# AVR128DB48_Curiosity_Nano_Target_MCU.net
KiCad netlist of a schematic drawn in Altium Designer
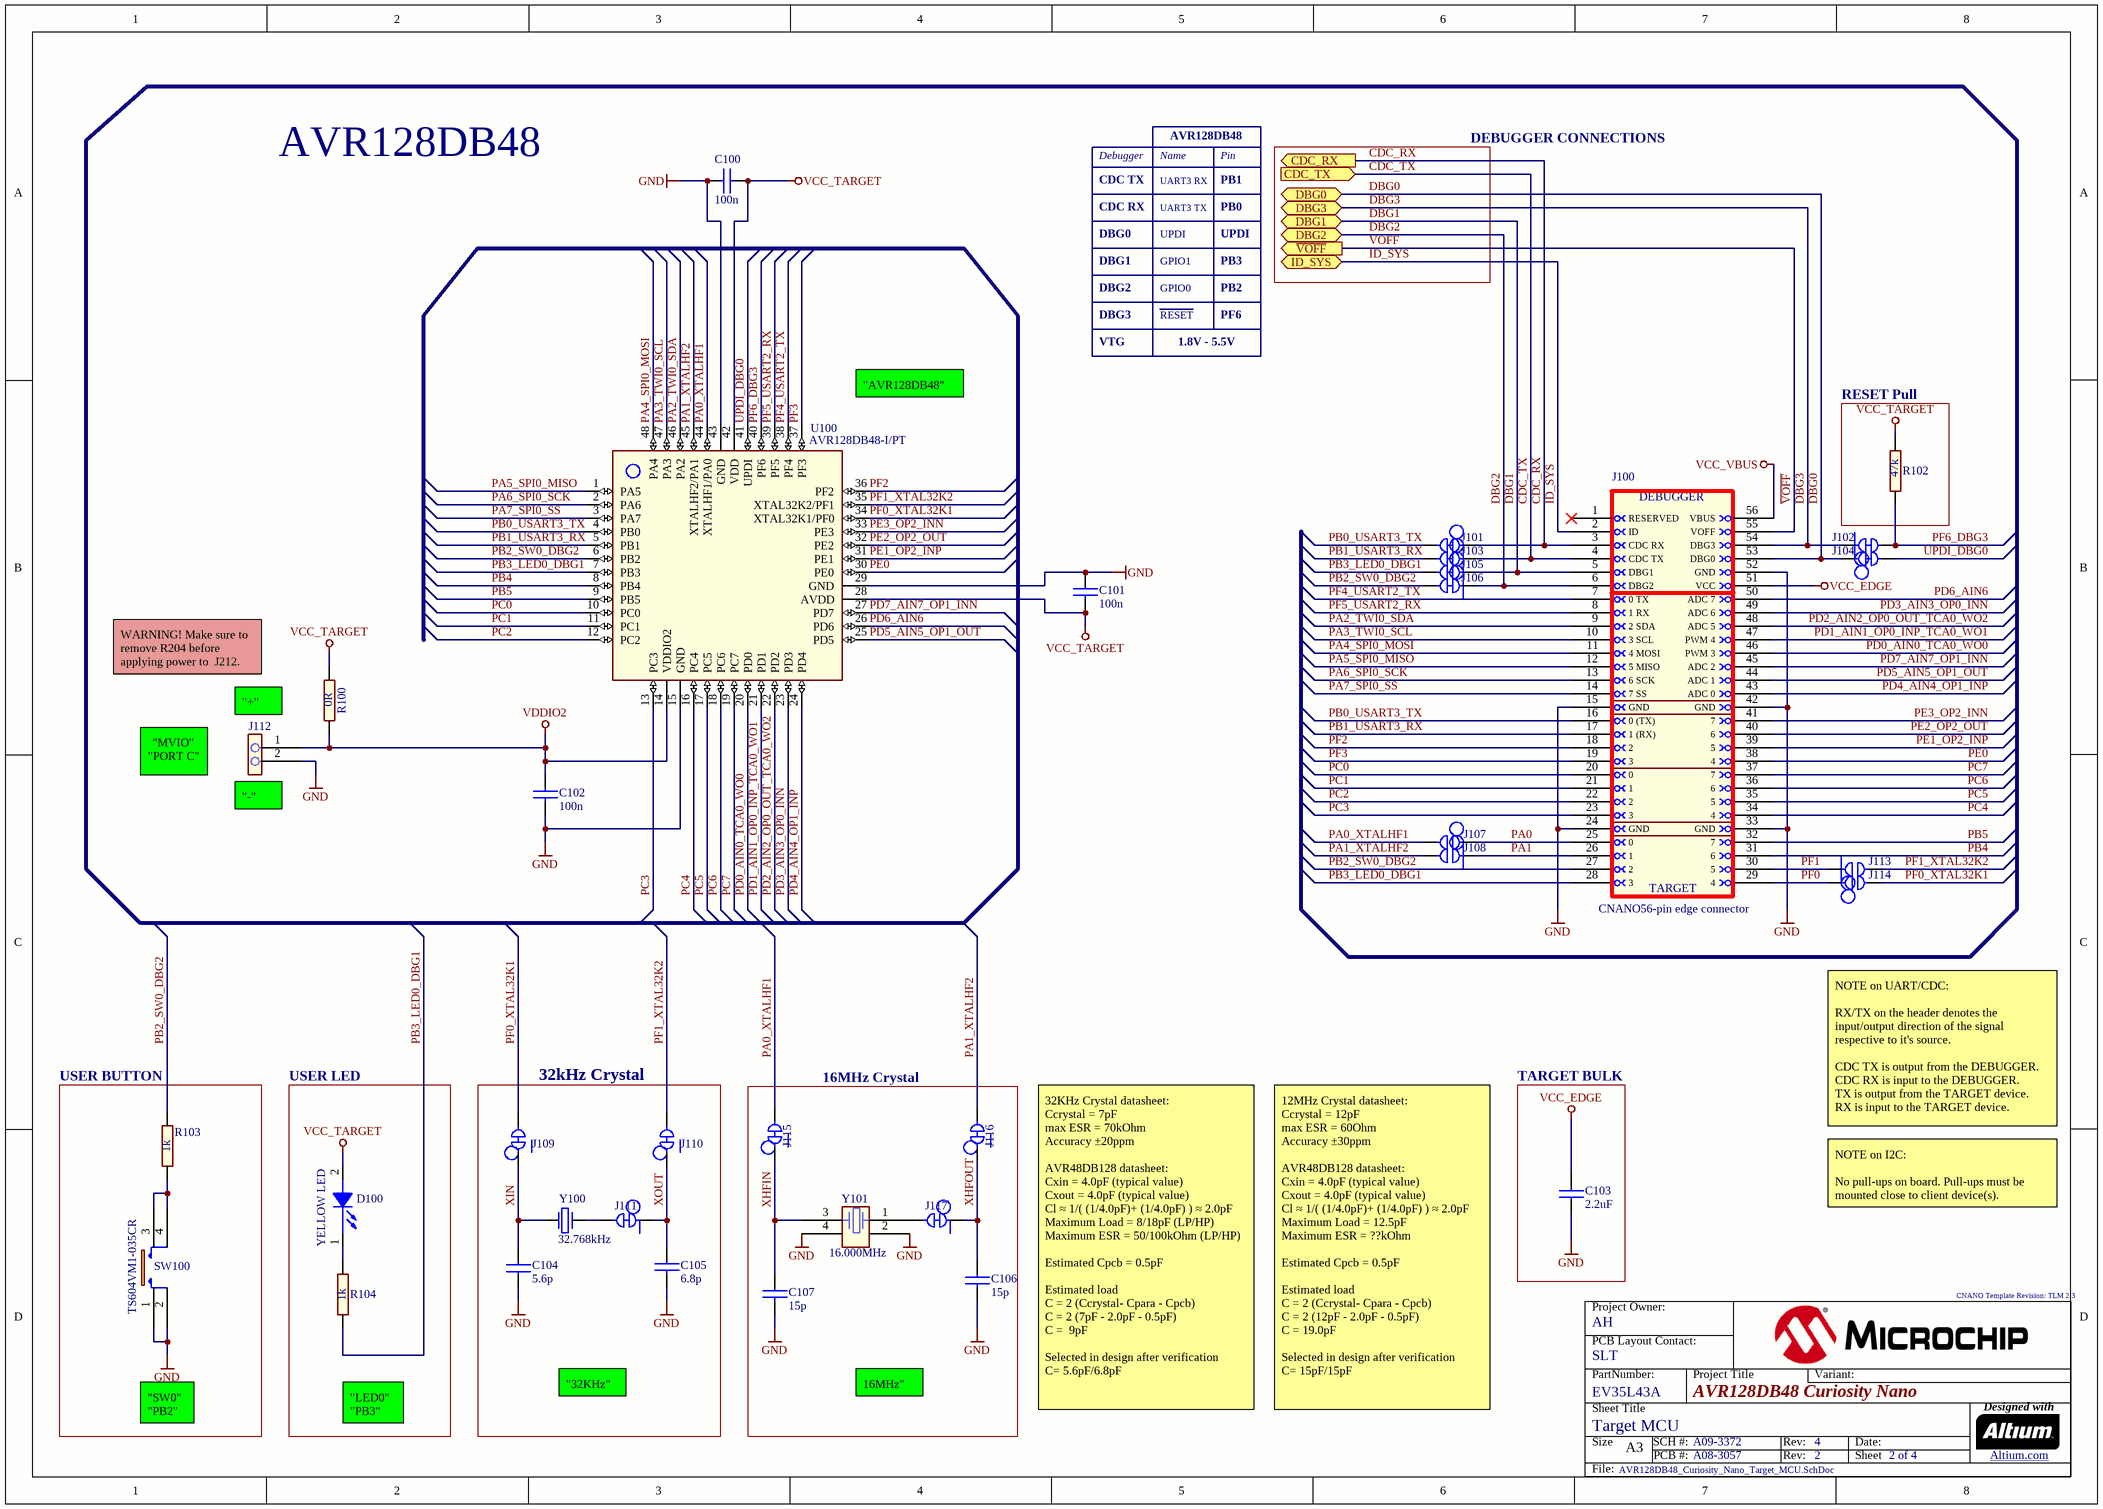
[diagram p0: AVR128DB48_Curiosity_Nano_Target_MCU.SchDoc]

(export (version "E")
  (design (tool "Eeschema 10.0.6"))
  (components
    (comp (ref "C100")
      (value "100n")
      (footprint "AP1-00148")
      (description "Ceramic capacitor, SMD 0402, X7R, 16V, +/-10%")
      (fields (field (name "MANUFACTURER") "Yageo") (field (name "MPN") "CC0402KRX7R7BB104"))
      (libsource (lib "AltiumDbLib") (part "CAP-NONPOL"))
    )
    (comp (ref "C101")
      (value "100n")
      (footprint "AP1-00148")
      (description "Ceramic capacitor, SMD 0402, X7R, 16V, +/-10%")
      (fields (field (name "MANUFACTURER") "Yageo") (field (name "MPN") "CC0402KRX7R7BB104"))
      (libsource (lib "AltiumDbLib") (part "CAP-NONPOL"))
    )
    (comp (ref "C102")
      (value "100n")
      (footprint "AP1-00148")
      (description "Ceramic capacitor, SMD 0402, X7R, 16V, +/-10%")
      (fields (field (name "MANUFACTURER") "Yageo") (field (name "MPN") "CC0402KRX7R7BB104"))
      (libsource (lib "AltiumDbLib") (part "CAP-NONPOL"))
    )
    (comp (ref "C103")
      (value "2.2uF")
      (footprint "AP1-00148")
      (description "CAP CER 2.2UF 10V 10% X5R 0402")
      (fields (field (name "TOLERANCE") "+/-10%") (field (name "MANUFACTURER") "TDK"))
      (libsource (lib "AltiumDbLib") (part "CAP-NONPOL"))
    )
    (comp (ref "C104")
      (value "5.6p")
      (footprint "AP1-00148")
      (description "Ceramic capacitor, SMD 0402, NP0, 50V, +/-5%")
      (fields (field (name "TOLERANCE") "50V, +/-5%") (field (name "MANUFACTURER") "Yageo"))
      (libsource (lib "AltiumDbLib") (part "CAP-NONPOL"))
    )
    (comp (ref "C105")
      (value "6.8p")
      (footprint "AP1-00148")
      (description "Ceramic capacitor, SMD 0402, NP0, 50V, +/-5%")
      (fields (field (name "TOLERANCE") "50V, +/-5%") (field (name "MANUFACTURER") "Yageo"))
      (libsource (lib "AltiumDbLib") (part "CAP-NONPOL"))
    )
    (comp (ref "C106")
      (value "15p")
      (footprint "AP1-00148")
      (description "Ceramic capacitor, SMD 0402, NP0, 50V, +/-5%")
      (fields (field (name "MANUFACTURER") "Yageo") (field (name "MPN") "CC0402JRNPO9BN150"))
      (libsource (lib "AltiumDbLib") (part "CAP-NONPOL"))
    )
    (comp (ref "C107")
      (value "15p")
      (footprint "AP1-00148")
      (description "Ceramic capacitor, SMD 0402, NP0, 50V, +/-5%")
      (fields (field (name "MANUFACTURER") "Yageo") (field (name "MPN") "CC0402JRNPO9BN150"))
      (libsource (lib "AltiumDbLib") (part "CAP-NONPOL"))
    )
    (comp (ref "D100")
      (value "YELLOW LED")
      (footprint "AP4-00169")
      (description "LED, SMD 0603, Yellow, Wave length=590nm, 100mcd @ (20mA, 2.2Vf) rohm")
      (fields (field (name "MANUFACTURER") "ROHM") (field (name "MPN") "SML-D12Y1WT86"))
      (libsource (lib "AltiumDbLib") (part "LED_12"))
    )
    (comp (ref "J100")
      (value "CNANO56-pin edge connector")
      (footprint "AP8-01100")
      (description "Curiosity Nano 56-pin edge connector with castellations, 100-mil pitch.")
      (libsource (lib "AltiumDbLib") (part "CNANO_Connector_56"))
    )
    (comp (ref "J101")
      (value "~")
      (footprint "AP8-01166")
      (description "Closed Link 0402 w/50mil hole")
      (libsource (lib "") (part "SMD-STRAP_CLOSED_1"))
    )
    (comp (ref "J102")
      (value "~")
      (footprint "AP8-01166")
      (description "Closed Link 0402 w/50mil hole")
      (libsource (lib "") (part "SMD-STRAP_CLOSED_1"))
    )
    (comp (ref "J103")
      (value "~")
      (footprint "AP8-01166")
      (description "Closed Link 0402 w/50mil hole")
      (libsource (lib "") (part "SMD-STRAP_CLOSED_1"))
    )
    (comp (ref "J104")
      (value "~")
      (footprint "AP8-01166")
      (description "Closed Link 0402 w/50mil hole")
      (libsource (lib "") (part "SMD-STRAP_CLOSED_1"))
    )
    (comp (ref "J105")
      (value "~")
      (footprint "AP8-01166")
      (description "Closed Link 0402 w/50mil hole")
      (libsource (lib "") (part "SMD-STRAP_CLOSED_1"))
    )
    (comp (ref "J106")
      (value "~")
      (footprint "AP8-01166")
      (description "Closed Link 0402 w/50mil hole")
      (libsource (lib "") (part "SMD-STRAP_CLOSED_1"))
    )
    (comp (ref "J107")
      (value "~")
      (footprint "AP9-00172")
      (description "1x1mm, Round Strap, Open, no frame")
      (libsource (lib "AltiumDbLib") (part "SMD-STRAP_OPEN"))
    )
    (comp (ref "J108")
      (value "~")
      (footprint "AP9-00172")
      (description "1x1mm, Round Strap, Open, no frame")
      (libsource (lib "AltiumDbLib") (part "SMD-STRAP_OPEN"))
    )
    (comp (ref "J109")
      (value "~")
      (footprint "AP8-01166")
      (description "Closed Link 0402 w/50mil hole")
      (libsource (lib "") (part "SMD-STRAP_CLOSED_1"))
    )
    (comp (ref "J110")
      (value "~")
      (footprint "AP8-01166")
      (description "Closed Link 0402 w/50mil hole")
      (libsource (lib "") (part "SMD-STRAP_CLOSED_1"))
    )
    (comp (ref "J111")
      (value "~")
      (footprint "AP8-00595")
      (description "Closed Link 0402")
      (libsource (lib "AltiumDbLib") (part "SMD-STRAP_CLOSED"))
    )
    (comp (ref "J112")
      (value "~")
      (footprint "AP8-01074")
      (description "1x2 pin header, 2.54mm pitch, Pin-in-Paste THM")
      (fields (field (name "MANUFACTURER") "Cabcon A/S") (field (name "MPN") "1125-1102S0S113CR01"))
      (libsource (lib "AltiumDbLib") (part "HEADER 1x2"))
    )
    (comp (ref "J113")
      (value "~")
      (footprint "AP9-00172")
      (description "1x1mm, Round Strap, Open, no frame")
      (libsource (lib "AltiumDbLib") (part "SMD-STRAP_OPEN"))
    )
    (comp (ref "J114")
      (value "~")
      (footprint "AP9-00172")
      (description "1x1mm, Round Strap, Open, no frame")
      (libsource (lib "AltiumDbLib") (part "SMD-STRAP_OPEN"))
    )
    (comp (ref "J115")
      (value "~")
      (footprint "AP8-01166")
      (description "Closed Link 0402 w/50mil hole")
      (libsource (lib "") (part "SMD-STRAP_CLOSED_1"))
    )
    (comp (ref "J116")
      (value "~")
      (footprint "AP8-01166")
      (description "Closed Link 0402 w/50mil hole")
      (libsource (lib "") (part "SMD-STRAP_CLOSED_1"))
    )
    (comp (ref "J117")
      (value "~")
      (footprint "AP8-00595")
      (description "Closed Link 0402")
      (libsource (lib "AltiumDbLib") (part "SMD-STRAP_CLOSED"))
    )
    (comp (ref "R100")
      (value "0R")
      (footprint "AP2-00108")
      (description "RES 0.0 OHM 1/16W 0402 SMD")
      (fields (field (name "TOLERANCE") "1 %") (field (name "MANUFACTURER") "Yageo"))
      (libsource (lib "AltiumDbLib") (part "R2"))
    )
    (comp (ref "R102")
      (value "47k")
      (footprint "AP2-00108")
      (description "Thick film resistor, SMD 0402, 1/16W, 1%")
      (fields (field (name "TOLERANCE") "1 %") (field (name "MANUFACTURER") "KOA"))
      (libsource (lib "AltiumDbLib") (part "R2"))
    )
    (comp (ref "R103")
      (value "1k")
      (footprint "AP2-00108")
      (description "Thick film resistor, SMD 0402, 1/16W, 1%")
      (fields (field (name "TOLERANCE") "1 %") (field (name "MANUFACTURER") "Yageo"))
      (libsource (lib "") (part "R2_1"))
    )
    (comp (ref "R104")
      (value "1k")
      (footprint "AP2-00108")
      (description "Thick film resistor, SMD 0402, 1/16W, 1%")
      (fields (field (name "TOLERANCE") "1 %") (field (name "MANUFACTURER") "Yageo"))
      (libsource (lib "AltiumDbLib") (part "R2"))
    )
    (comp (ref "SW100")
      (value "TS604VM1-035CR")
      (footprint "AP8-00137")
      (description "SWITCH, SMD, 260gf, 6.4mm X 6.2mm")
      (fields
        (field (name "MANUFACTURER") "Dailywell Electronics Co.LTD")
        (field (name "MPN") "TS604VM1-035CR-R")
      )
      (libsource (lib "AltiumDbLib") (part "PUSHBUTTON1"))
    )
    (comp (ref "U100")
      (value "AVR128DB48-I/PT")
      (footprint "AP6-00357")
      (description "AVR MCU 8-Bit 128kB Flash 48 pin 24MHz TQFP")
      (fields (field (name "MANUFACTURER") "Microchip") (field (name "MPN") "AVR128DB48T-I/PT"))
      (libsource (lib "AltiumDbLib") (part "AVR128DB48_TQFP"))
    )
    (comp (ref "Y100")
      (value "32.768kHz")
      (footprint "AP7-00069")
      (description "Crystal, 32.768kHz, CL=7.0pF, ESR=70kOhm, SMD  LxW=3.2 x 1.5mm, 20ppm")
      (fields (field (name "MANUFACTURER") "Microchip") (field (name "MPN") "VMK3-9002-32K7680000TR"))
      (libsource (lib "AltiumDbLib") (part "CRYSTAL"))
    )
    (comp (ref "Y101")
      (value "16.000MHz")
      (footprint "AP7-00061")
      (description "Crystal, 16.0MHz, CL=12.0pF, ESR=80Ohm, SMD  LxW=3.2 x 25mm, 20ppm")
      (fields (field (name "TOLERANCE") "20ppm") (field (name "MANUFACTURER") "Microchip"))
      (libsource (lib "AltiumDbLib") (part "CRYSTAL1324"))
    )
  )
  (nets
    (net (code "1") (name "/CDC_RX") (class "Default")
      (node (ref "J100") (pin "3") (pinfunction "CDC_RX_3") (pintype "passive"))
      (node (ref "J101") (pin "1") (pinfunction "1_1") (pintype "passive"))
    )
    (net (code "2") (name "/CDC_TX") (class "Default")
      (node (ref "J100") (pin "4") (pinfunction "CDC_TX_4") (pintype "passive"))
      (node (ref "J103") (pin "1") (pinfunction "1_1") (pintype "passive"))
    )
    (net (code "3") (name "/DBG0") (class "Default")
      (node (ref "J100") (pin "53") (pinfunction "DBG0_53") (pintype "passive"))
      (node (ref "J104") (pin "1") (pinfunction "1_1") (pintype "passive"))
    )
    (net (code "4") (name "/DBG1") (class "Default")
      (node (ref "J100") (pin "5") (pinfunction "DBG1_5") (pintype "passive"))
      (node (ref "J105") (pin "1") (pinfunction "1_1") (pintype "passive"))
    )
    (net (code "5") (name "/DBG2") (class "Default")
      (node (ref "J100") (pin "6") (pinfunction "DBG2_6") (pintype "passive"))
      (node (ref "J106") (pin "1") (pinfunction "1_1") (pintype "passive"))
    )
    (net (code "6") (name "/DBG3") (class "Default")
      (node (ref "J100") (pin "54") (pinfunction "DBG3_54") (pintype "passive"))
      (node (ref "J102") (pin "1") (pinfunction "1_1") (pintype "passive"))
    )
    (net (code "7") (name "/ID_SYS") (class "Default")
      (node (ref "J100") (pin "2") (pinfunction "ID_2") (pintype "passive"))
    )
    (net (code "8") (name "/PA0") (class "Default")
      (node (ref "J100") (pin "25") (pinfunction "0_25") (pintype "passive"))
      (node (ref "J107") (pin "1") (pinfunction "1_1") (pintype "passive"))
    )
    (net (code "9") (name "/PA0_XTALHF1") (class "Default")
      (node (ref "J107") (pin "2") (pinfunction "2_2") (pintype "passive"))
      (node (ref "J115") (pin "2") (pinfunction "2_2") (pintype "passive"))
      (node (ref "U100") (pin "44") (pinfunction "XTALHF1/PA0_44") (pintype "bidirectional"))
    )
    (net (code "10") (name "/PA1") (class "Default")
      (node (ref "J100") (pin "26") (pinfunction "1_26") (pintype "passive"))
      (node (ref "J108") (pin "1") (pinfunction "1_1") (pintype "passive"))
    )
    (net (code "11") (name "/PA1_XTALHF2") (class "Default")
      (node (ref "J108") (pin "2") (pinfunction "2_2") (pintype "passive"))
      (node (ref "J116") (pin "2") (pinfunction "2_2") (pintype "passive"))
      (node (ref "U100") (pin "45") (pinfunction "XTALHF2/PA1_45") (pintype "bidirectional"))
    )
    (net (code "12") (name "/PA2_TWI0_SDA") (class "Default")
      (node (ref "J100") (pin "9") (pinfunction "2_SDA_9") (pintype "passive"))
      (node (ref "U100") (pin "46") (pinfunction "PA2_46") (pintype "bidirectional"))
    )
    (net (code "13") (name "/PA3_TWI0_SCL") (class "Default")
      (node (ref "J100") (pin "10") (pinfunction "3_SCL_10") (pintype "passive"))
      (node (ref "U100") (pin "47") (pinfunction "PA3_47") (pintype "bidirectional"))
    )
    (net (code "14") (name "/PA4_SPI0_MOSI") (class "Default")
      (node (ref "J100") (pin "11") (pinfunction "4_MOSI_11") (pintype "passive"))
      (node (ref "U100") (pin "48") (pinfunction "PA4_48") (pintype "bidirectional"))
    )
    (net (code "15") (name "/PA5_SPI0_MISO") (class "Default")
      (node (ref "J100") (pin "12") (pinfunction "5_MISO_12") (pintype "passive"))
      (node (ref "U100") (pin "1") (pinfunction "PA5_1") (pintype "bidirectional"))
    )
    (net (code "16") (name "/PA6_SPI0_SCK") (class "Default")
      (node (ref "J100") (pin "13") (pinfunction "6_SCK_13") (pintype "passive"))
      (node (ref "U100") (pin "2") (pinfunction "PA6_2") (pintype "bidirectional"))
    )
    (net (code "17") (name "/PA7_SPI0_SS") (class "Default")
      (node (ref "J100") (pin "14") (pinfunction "7_SS_14") (pintype "passive"))
      (node (ref "U100") (pin "3") (pinfunction "PA7_3") (pintype "bidirectional"))
    )
    (net (code "18") (name "/PB0_USART3_TX") (class "Default")
      (node (ref "J100") (pin "16") (pinfunction "0_(TX)_16") (pintype "passive"))
      (node (ref "J101") (pin "2") (pinfunction "2_2") (pintype "passive"))
      (node (ref "U100") (pin "4") (pinfunction "PB0_4") (pintype "bidirectional"))
    )
    (net (code "19") (name "/PB1_USART3_RX") (class "Default")
      (node (ref "J100") (pin "17") (pinfunction "1_(RX)_17") (pintype "passive"))
      (node (ref "J103") (pin "2") (pinfunction "2_2") (pintype "passive"))
      (node (ref "U100") (pin "5") (pinfunction "PB1_5") (pintype "bidirectional"))
    )
    (net (code "20") (name "/PB2_SW0_DBG2") (class "Default")
      (node (ref "J100") (pin "27") (pinfunction "2_27") (pintype "passive"))
      (node (ref "J106") (pin "2") (pinfunction "2_2") (pintype "passive"))
      (node (ref "R103") (pin "1") (pinfunction "1_1") (pintype "passive"))
      (node (ref "U100") (pin "6") (pinfunction "PB2_6") (pintype "bidirectional"))
    )
    (net (code "21") (name "/PB3_LED0_DBG1") (class "Default")
      (node (ref "J100") (pin "28") (pinfunction "3_28") (pintype "passive"))
      (node (ref "J105") (pin "2") (pinfunction "2_2") (pintype "passive"))
      (node (ref "R104") (pin "1") (pinfunction "1_1") (pintype "passive"))
      (node (ref "U100") (pin "7") (pinfunction "PB3_7") (pintype "bidirectional"))
    )
    (net (code "22") (name "/PB4") (class "Default")
      (node (ref "J100") (pin "31") (pinfunction "6_31") (pintype "passive"))
      (node (ref "U100") (pin "8") (pinfunction "PB4_8") (pintype "bidirectional"))
    )
    (net (code "23") (name "/PB5") (class "Default")
      (node (ref "J100") (pin "32") (pinfunction "7_32") (pintype "passive"))
      (node (ref "U100") (pin "9") (pinfunction "PB5_9") (pintype "bidirectional"))
    )
    (net (code "24") (name "/PC0") (class "Default")
      (node (ref "J100") (pin "20") (pinfunction "0_20") (pintype "passive"))
      (node (ref "U100") (pin "10") (pinfunction "PC0_10") (pintype "bidirectional"))
    )
    (net (code "25") (name "/PC1") (class "Default")
      (node (ref "J100") (pin "21") (pinfunction "1_21") (pintype "passive"))
      (node (ref "U100") (pin "11") (pinfunction "PC1_11") (pintype "bidirectional"))
    )
    (net (code "26") (name "/PC2") (class "Default")
      (node (ref "J100") (pin "22") (pinfunction "2_22") (pintype "passive"))
      (node (ref "U100") (pin "12") (pinfunction "PC2_12") (pintype "bidirectional"))
    )
    (net (code "27") (name "/PC3") (class "Default")
      (node (ref "J100") (pin "23") (pinfunction "3_23") (pintype "passive"))
      (node (ref "U100") (pin "13") (pinfunction "PC3_13") (pintype "bidirectional"))
    )
    (net (code "28") (name "/PC4") (class "Default")
      (node (ref "J100") (pin "34") (pinfunction "4_34") (pintype "passive"))
      (node (ref "U100") (pin "16") (pinfunction "PC4_16") (pintype "bidirectional"))
    )
    (net (code "29") (name "/PC5") (class "Default")
      (node (ref "J100") (pin "35") (pinfunction "5_35") (pintype "passive"))
      (node (ref "U100") (pin "17") (pinfunction "PC5_17") (pintype "bidirectional"))
    )
    (net (code "30") (name "/PC6") (class "Default")
      (node (ref "J100") (pin "36") (pinfunction "6_36") (pintype "passive"))
      (node (ref "U100") (pin "18") (pinfunction "PC6_18") (pintype "bidirectional"))
    )
    (net (code "31") (name "/PC7") (class "Default")
      (node (ref "J100") (pin "37") (pinfunction "7_37") (pintype "passive"))
      (node (ref "U100") (pin "19") (pinfunction "PC7_19") (pintype "bidirectional"))
    )
    (net (code "32") (name "/PD0_AIN0_TCA0_WO0") (class "Default")
      (node (ref "J100") (pin "46") (pinfunction "PWM_3_46") (pintype "passive"))
      (node (ref "U100") (pin "20") (pinfunction "PD0_20") (pintype "bidirectional"))
    )
    (net (code "33") (name "/PD1_AIN1_OP0_INP_TCA0_WO1") (class "Default")
      (node (ref "J100") (pin "47") (pinfunction "PWM_4_47") (pintype "passive"))
      (node (ref "U100") (pin "21") (pinfunction "PD1_21") (pintype "bidirectional"))
    )
    (net (code "34") (name "/PD2_AIN2_OP0_OUT_TCA0_WO2") (class "Default")
      (node (ref "J100") (pin "48") (pinfunction "ADC_5_48") (pintype "passive"))
      (node (ref "U100") (pin "22") (pinfunction "PD2_22") (pintype "bidirectional"))
    )
    (net (code "35") (name "/PD3_AIN3_OP0_INN") (class "Default")
      (node (ref "J100") (pin "49") (pinfunction "ADC_6_49") (pintype "passive"))
      (node (ref "U100") (pin "23") (pinfunction "PD3_23") (pintype "bidirectional"))
    )
    (net (code "36") (name "/PD4_AIN4_OP1_INP") (class "Default")
      (node (ref "J100") (pin "43") (pinfunction "ADC_0_43") (pintype "passive"))
      (node (ref "U100") (pin "24") (pinfunction "PD4_24") (pintype "bidirectional"))
    )
    (net (code "37") (name "/PD5_AIN5_OP1_OUT") (class "Default")
      (node (ref "J100") (pin "44") (pinfunction "ADC_1_44") (pintype "passive"))
      (node (ref "U100") (pin "25") (pinfunction "PD5_25") (pintype "bidirectional"))
    )
    (net (code "38") (name "/PD6_AIN6") (class "Default")
      (node (ref "J100") (pin "50") (pinfunction "ADC_7_50") (pintype "passive"))
      (node (ref "U100") (pin "26") (pinfunction "PD6_26") (pintype "bidirectional"))
    )
    (net (code "39") (name "/PD7_AIN7_OP1_INN") (class "Default")
      (node (ref "J100") (pin "45") (pinfunction "ADC_2_45") (pintype "passive"))
      (node (ref "U100") (pin "27") (pinfunction "PD7_27") (pintype "bidirectional"))
    )
    (net (code "40") (name "/PE0") (class "Default")
      (node (ref "J100") (pin "38") (pinfunction "4_38") (pintype "passive"))
      (node (ref "U100") (pin "30") (pinfunction "PE0_30") (pintype "bidirectional"))
    )
    (net (code "41") (name "/PE1_OP2_INP") (class "Default")
      (node (ref "J100") (pin "39") (pinfunction "5_39") (pintype "passive"))
      (node (ref "U100") (pin "31") (pinfunction "PE1_31") (pintype "bidirectional"))
    )
    (net (code "42") (name "/PE2_OP2_OUT") (class "Default")
      (node (ref "J100") (pin "40") (pinfunction "6_40") (pintype "passive"))
      (node (ref "U100") (pin "32") (pinfunction "PE2_32") (pintype "bidirectional"))
    )
    (net (code "43") (name "/PE3_OP2_INN") (class "Default")
      (node (ref "J100") (pin "41") (pinfunction "7_41") (pintype "passive"))
      (node (ref "U100") (pin "33") (pinfunction "PE3_33") (pintype "bidirectional"))
    )
    (net (code "44") (name "/PF0") (class "Default")
      (node (ref "J100") (pin "29") (pinfunction "4_29") (pintype "passive"))
      (node (ref "J114") (pin "1") (pinfunction "1_1") (pintype "passive"))
    )
    (net (code "45") (name "/PF0_XTAL32K1") (class "Default")
      (node (ref "J109") (pin "2") (pinfunction "2_2") (pintype "passive"))
      (node (ref "J114") (pin "2") (pinfunction "2_2") (pintype "passive"))
      (node (ref "U100") (pin "34") (pinfunction "XTAL32K1/PF0_34") (pintype "bidirectional"))
    )
    (net (code "46") (name "/PF1") (class "Default")
      (node (ref "J100") (pin "30") (pinfunction "5_30") (pintype "passive"))
      (node (ref "J113") (pin "1") (pinfunction "1_1") (pintype "passive"))
    )
    (net (code "47") (name "/PF1_XTAL32K2") (class "Default")
      (node (ref "J110") (pin "2") (pinfunction "2_2") (pintype "passive"))
      (node (ref "J113") (pin "2") (pinfunction "2_2") (pintype "passive"))
      (node (ref "U100") (pin "35") (pinfunction "XTAL32K2/PF1_35") (pintype "bidirectional"))
    )
    (net (code "48") (name "/PF2") (class "Default")
      (node (ref "J100") (pin "18") (pinfunction "2_18") (pintype "passive"))
      (node (ref "U100") (pin "36") (pinfunction "PF2_36") (pintype "bidirectional"))
    )
    (net (code "49") (name "/PF3") (class "Default")
      (node (ref "J100") (pin "19") (pinfunction "3_19") (pintype "passive"))
      (node (ref "U100") (pin "37") (pinfunction "PF3_37") (pintype "bidirectional"))
    )
    (net (code "50") (name "/PF4_USART2_TX") (class "Default")
      (node (ref "J100") (pin "7") (pinfunction "0_TX_7") (pintype "passive"))
      (node (ref "U100") (pin "38") (pinfunction "PF4_38") (pintype "bidirectional"))
    )
    (net (code "51") (name "/PF5_USART2_RX") (class "Default")
      (node (ref "J100") (pin "8") (pinfunction "1_RX_8") (pintype "passive"))
      (node (ref "U100") (pin "39") (pinfunction "PF5_39") (pintype "bidirectional"))
    )
    (net (code "52") (name "/PF6_DBG3") (class "Default")
      (node (ref "J102") (pin "2") (pinfunction "2_2") (pintype "passive"))
      (node (ref "R102") (pin "1") (pinfunction "1_1") (pintype "passive"))
      (node (ref "U100") (pin "40") (pinfunction "PF6_40") (pintype "bidirectional"))
    )
    (net (code "53") (name "/UPDI_DBG0") (class "Default")
      (node (ref "J104") (pin "2") (pinfunction "2_2") (pintype "passive"))
      (node (ref "U100") (pin "41") (pinfunction "UPDI_41") (pintype "bidirectional"))
    )
    (net (code "54") (name "/XHFIN") (class "Default")
      (node (ref "C107") (pin "1") (pinfunction "1_1") (pintype "passive"))
      (node (ref "J115") (pin "1") (pinfunction "1_1") (pintype "passive"))
      (node (ref "Y101") (pin "3") (pinfunction "3_3") (pintype "passive"))
    )
    (net (code "55") (name "/XHFOUT") (class "Default")
      (node (ref "C106") (pin "1") (pinfunction "1_1") (pintype "passive"))
      (node (ref "J116") (pin "1") (pinfunction "1_1") (pintype "passive"))
      (node (ref "J117") (pin "1") (pinfunction "1_1") (pintype "passive"))
    )
    (net (code "56") (name "/XIN") (class "Default")
      (node (ref "C104") (pin "2") (pinfunction "2_2") (pintype "passive"))
      (node (ref "J109") (pin "1") (pinfunction "1_1") (pintype "passive"))
      (node (ref "Y100") (pin "1") (pinfunction "1_1") (pintype "passive"))
    )
    (net (code "57") (name "/XOUT") (class "Default")
      (node (ref "C105") (pin "1") (pinfunction "1_1") (pintype "passive"))
      (node (ref "J110") (pin "1") (pinfunction "1_1") (pintype "passive"))
      (node (ref "J111") (pin "1") (pinfunction "1_1") (pintype "passive"))
    )
    (net (code "58") (name "/~{VOFF}") (class "Default")
      (node (ref "J100") (pin "55") (pinfunction "VOFF_55") (pintype "passive"))
    )
    (net (code "59") (name "GND") (class "Default")
      (node (ref "C100") (pin "1") (pinfunction "1_1") (pintype "passive"))
      (node (ref "C101") (pin "1") (pinfunction "1_1") (pintype "passive"))
      (node (ref "C102") (pin "2") (pinfunction "2_2") (pintype "passive"))
      (node (ref "C103") (pin "1") (pinfunction "1_1") (pintype "passive"))
      (node (ref "C104") (pin "1") (pinfunction "1_1") (pintype "passive"))
      (node (ref "C105") (pin "2") (pinfunction "2_2") (pintype "passive"))
      (node (ref "C106") (pin "2") (pinfunction "2_2") (pintype "passive"))
      (node (ref "C107") (pin "2") (pinfunction "2_2") (pintype "passive"))
      (node (ref "J100") (pin "15") (pinfunction "GND_15") (pintype "power_in"))
      (node (ref "J100") (pin "24") (pinfunction "GND_24") (pintype "power_in"))
      (node (ref "J100") (pin "33") (pinfunction "GND_33") (pintype "power_in"))
      (node (ref "J100") (pin "42") (pinfunction "GND_42") (pintype "power_in"))
      (node (ref "J100") (pin "52") (pinfunction "GND_52") (pintype "power_in"))
      (node (ref "J112") (pin "2") (pinfunction "2_2") (pintype "passive"))
      (node (ref "SW100") (pin "1") (pinfunction "1_1") (pintype "passive"))
      (node (ref "SW100") (pin "2") (pinfunction "2_2") (pintype "passive"))
      (node (ref "U100") (pin "15") (pinfunction "GND_15") (pintype "power_in"))
      (node (ref "U100") (pin "29") (pinfunction "GND_29") (pintype "power_in"))
      (node (ref "U100") (pin "43") (pinfunction "GND_43") (pintype "power_in"))
      (node (ref "Y101") (pin "2") (pinfunction "2_2") (pintype "passive"))
      (node (ref "Y101") (pin "4") (pinfunction "4_4") (pintype "passive"))
    )
    (net (code "60") (name "Net-(D100-CATHODE)") (class "Default")
      (node (ref "D100") (pin "1") (pinfunction "CATHODE_1") (pintype "passive"))
      (node (ref "R104") (pin "2") (pinfunction "2_2") (pintype "passive"))
    )
    (net (code "61") (name "Net-(J111-Pad2)") (class "Default")
      (node (ref "J111") (pin "2") (pinfunction "2_2") (pintype "passive"))
      (node (ref "Y100") (pin "2") (pinfunction "2_2") (pintype "passive"))
    )
    (net (code "62") (name "Net-(J117-Pad2)") (class "Default")
      (node (ref "J117") (pin "2") (pinfunction "2_2") (pintype "passive"))
      (node (ref "Y101") (pin "1") (pinfunction "1_1") (pintype "passive"))
    )
    (net (code "63") (name "Net-(R103-Pad2)") (class "Default")
      (node (ref "R103") (pin "2") (pinfunction "2_2") (pintype "passive"))
      (node (ref "SW100") (pin "3") (pinfunction "3_3") (pintype "passive"))
      (node (ref "SW100") (pin "4") (pinfunction "4_4") (pintype "passive"))
    )
    (net (code "64") (name "VCC_EDGE") (class "Default")
      (node (ref "C103") (pin "2") (pinfunction "2_2") (pintype "passive"))
      (node (ref "J100") (pin "51") (pinfunction "VCC_51") (pintype "power_in"))
    )
    (net (code "65") (name "VCC_TARGET") (class "Default")
      (node (ref "C100") (pin "2") (pinfunction "2_2") (pintype "passive"))
      (node (ref "C101") (pin "2") (pinfunction "2_2") (pintype "passive"))
      (node (ref "D100") (pin "2") (pinfunction "ANODE_2") (pintype "passive"))
      (node (ref "R100") (pin "2") (pinfunction "2_2") (pintype "passive"))
      (node (ref "R102") (pin "2") (pinfunction "2_2") (pintype "passive"))
      (node (ref "U100") (pin "28") (pinfunction "AVDD_28") (pintype "power_in"))
      (node (ref "U100") (pin "42") (pinfunction "VDD_42") (pintype "power_in"))
    )
    (net (code "66") (name "VCC_VBUS") (class "Default")
      (node (ref "J100") (pin "56") (pinfunction "VBUS_56") (pintype "passive"))
    )
    (net (code "67") (name "VDDIO2") (class "Default")
      (node (ref "C102") (pin "1") (pinfunction "1_1") (pintype "passive"))
      (node (ref "J112") (pin "1") (pinfunction "1_1") (pintype "passive"))
      (node (ref "R100") (pin "1") (pinfunction "1_1") (pintype "passive"))
      (node (ref "U100") (pin "14") (pinfunction "VDDIO2_14") (pintype "power_in"))
    )
    (net (code "68") (name "unconnected-(J100-RESERVED-Pad1)") (class "Default")
      (node (ref "J100") (pin "1") (pinfunction "RESERVED_1") (pintype "passive+no_connect"))
    )
  )
)
